# esquematicov2.net
KiCad netlist of a schematic drawn in EAGLE
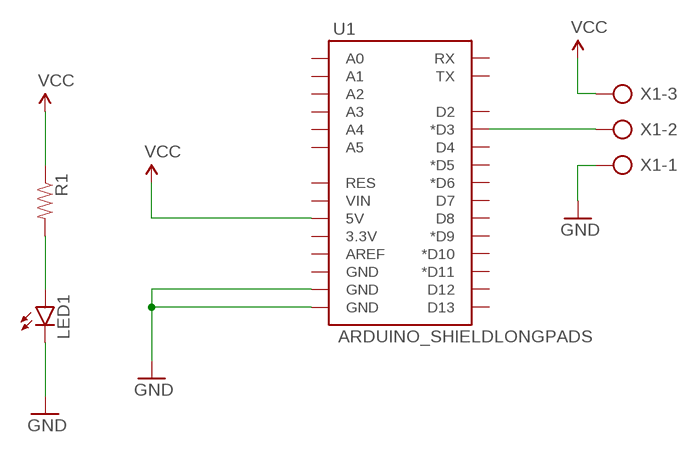
[diagram p0: schematic, sheet 1]

(export (version "E")
  (design (tool "Eeschema 10.0.6"))
  (components
    (comp (ref "LED1")
      (value "LED5MM")
      (footprint "eagle-import:LED5MM")
      (libsource (lib "eagle-import") (part "LED5MM"))
    )
    (comp (ref "R1")
      (value "RESISTORPTH-1/4W-VERT")
      (footprint "eagle-import:AXIAL-0.1")
      (libsource (lib "eagle-import") (part "RESISTORPTH-1/4W-VERT"))
    )
    (comp (ref "U1")
      (value "ARDUINO_SHIELDLONGPADS")
      (footprint "eagle-import:DUEMILANOVE_SHIELD_LONGPADS")
      (libsource (lib "eagle-import") (part "ARDUINO_SHIELDLONGPADS"))
    )
    (comp (ref "X1")
      (value "AK500/3-H")
      (footprint "eagle-import:AK500_3-H")
      (libsource (lib "eagle-import") (part "AK500/3-H"))
    )
  )
  (nets
    (net (code "1") (name "GND") (class "Default")
      (node (ref "LED1") (pin "K") (pinfunction "C_K") (pintype "passive"))
      (node (ref "U1") (pin "GND@0") (pinfunction "GND_GND@0") (pintype "bidirectional"))
      (node (ref "U1") (pin "GND@1") (pinfunction "GND_GND@1") (pintype "bidirectional"))
      (node (ref "X1") (pin "1") (pinfunction "KL_1") (pintype "passive"))
    )
    (net (code "2") (name "Net-(R1-2)") (class "Default")
      (node (ref "LED1") (pin "A") (pinfunction "A_A") (pintype "passive"))
      (node (ref "R1") (pin "P$2") (pinfunction "2_P$2") (pintype "passive"))
    )
    (net (code "3") (name "Net-(U1-*D3)") (class "Default")
      (node (ref "U1") (pin "D3") (pinfunction "*D3_D3") (pintype "bidirectional"))
      (node (ref "X1") (pin "2") (pinfunction "KL_2") (pintype "passive"))
    )
    (net (code "4") (name "VCC") (class "Default")
      (node (ref "R1") (pin "P$1") (pinfunction "1_P$1") (pintype "passive"))
      (node (ref "U1") (pin "5V") (pinfunction "5V_5V") (pintype "bidirectional"))
      (node (ref "X1") (pin "3") (pinfunction "KL_3") (pintype "passive"))
    )
    (net (code "5") (name "unconnected-(U1-*D5-PadD5)") (class "Default")
      (node (ref "U1") (pin "D5") (pinfunction "*D5_D5") (pintype "bidirectional"))
    )
    (net (code "6") (name "unconnected-(U1-*D6-PadD6)") (class "Default")
      (node (ref "U1") (pin "D6") (pinfunction "*D6_D6") (pintype "bidirectional"))
    )
    (net (code "7") (name "unconnected-(U1-*D9-PadD9)") (class "Default")
      (node (ref "U1") (pin "D9") (pinfunction "*D9_D9") (pintype "bidirectional"))
    )
    (net (code "8") (name "unconnected-(U1-*D10-PadD10)") (class "Default")
      (node (ref "U1") (pin "D10") (pinfunction "*D10_D10") (pintype "bidirectional"))
    )
    (net (code "9") (name "unconnected-(U1-*D11-PadD11)") (class "Default")
      (node (ref "U1") (pin "D11") (pinfunction "*D11_D11") (pintype "bidirectional"))
    )
    (net (code "10") (name "unconnected-(U1-GND-PadGND@2)") (class "Default")
      (node (ref "U1") (pin "GND@2") (pinfunction "GND_GND@2") (pintype "bidirectional"))
    )
    (net (code "11") (name "unconnected-(U1-Pad3.3V)") (class "Default")
      (node (ref "U1") (pin "3.3V") (pinfunction "3.3V_3.3V") (pintype "bidirectional"))
    )
    (net (code "12") (name "unconnected-(U1-PadA0)") (class "Default")
      (node (ref "U1") (pin "A0") (pinfunction "A0_A0") (pintype "bidirectional"))
    )
    (net (code "13") (name "unconnected-(U1-PadA1)") (class "Default")
      (node (ref "U1") (pin "A1") (pinfunction "A1_A1") (pintype "bidirectional"))
    )
    (net (code "14") (name "unconnected-(U1-PadA2)") (class "Default")
      (node (ref "U1") (pin "A2") (pinfunction "A2_A2") (pintype "bidirectional"))
    )
    (net (code "15") (name "unconnected-(U1-PadA3)") (class "Default")
      (node (ref "U1") (pin "A3") (pinfunction "A3_A3") (pintype "bidirectional"))
    )
    (net (code "16") (name "unconnected-(U1-PadA4)") (class "Default")
      (node (ref "U1") (pin "A4") (pinfunction "A4_A4") (pintype "bidirectional"))
    )
    (net (code "17") (name "unconnected-(U1-PadA5)") (class "Default")
      (node (ref "U1") (pin "A5") (pinfunction "A5_A5") (pintype "bidirectional"))
    )
    (net (code "18") (name "unconnected-(U1-PadAREF)") (class "Default")
      (node (ref "U1") (pin "AREF") (pinfunction "AREF_AREF") (pintype "bidirectional"))
    )
    (net (code "19") (name "unconnected-(U1-PadD2)") (class "Default")
      (node (ref "U1") (pin "D2") (pinfunction "D2_D2") (pintype "bidirectional"))
    )
    (net (code "20") (name "unconnected-(U1-PadD4)") (class "Default")
      (node (ref "U1") (pin "D4") (pinfunction "D4_D4") (pintype "bidirectional"))
    )
    (net (code "21") (name "unconnected-(U1-PadD7)") (class "Default")
      (node (ref "U1") (pin "D7") (pinfunction "D7_D7") (pintype "bidirectional"))
    )
    (net (code "22") (name "unconnected-(U1-PadD8)") (class "Default")
      (node (ref "U1") (pin "D8") (pinfunction "D8_D8") (pintype "bidirectional"))
    )
    (net (code "23") (name "unconnected-(U1-PadD12)") (class "Default")
      (node (ref "U1") (pin "D12") (pinfunction "D12_D12") (pintype "bidirectional"))
    )
    (net (code "24") (name "unconnected-(U1-PadD13)") (class "Default")
      (node (ref "U1") (pin "D13") (pinfunction "D13_D13") (pintype "bidirectional"))
    )
    (net (code "25") (name "unconnected-(U1-PadRES)") (class "Default")
      (node (ref "U1") (pin "RES") (pinfunction "RES_RES") (pintype "bidirectional"))
    )
    (net (code "26") (name "unconnected-(U1-PadRX)") (class "Default")
      (node (ref "U1") (pin "RX") (pinfunction "RX_RX") (pintype "bidirectional"))
    )
    (net (code "27") (name "unconnected-(U1-PadTX)") (class "Default")
      (node (ref "U1") (pin "TX") (pinfunction "TX_TX") (pintype "bidirectional"))
    )
    (net (code "28") (name "unconnected-(U1-PadVIN)") (class "Default")
      (node (ref "U1") (pin "VIN") (pinfunction "VIN_VIN") (pintype "bidirectional"))
    )
  )
)
